# Sheet1.net
KiCad netlist of a schematic drawn in Altium Designer
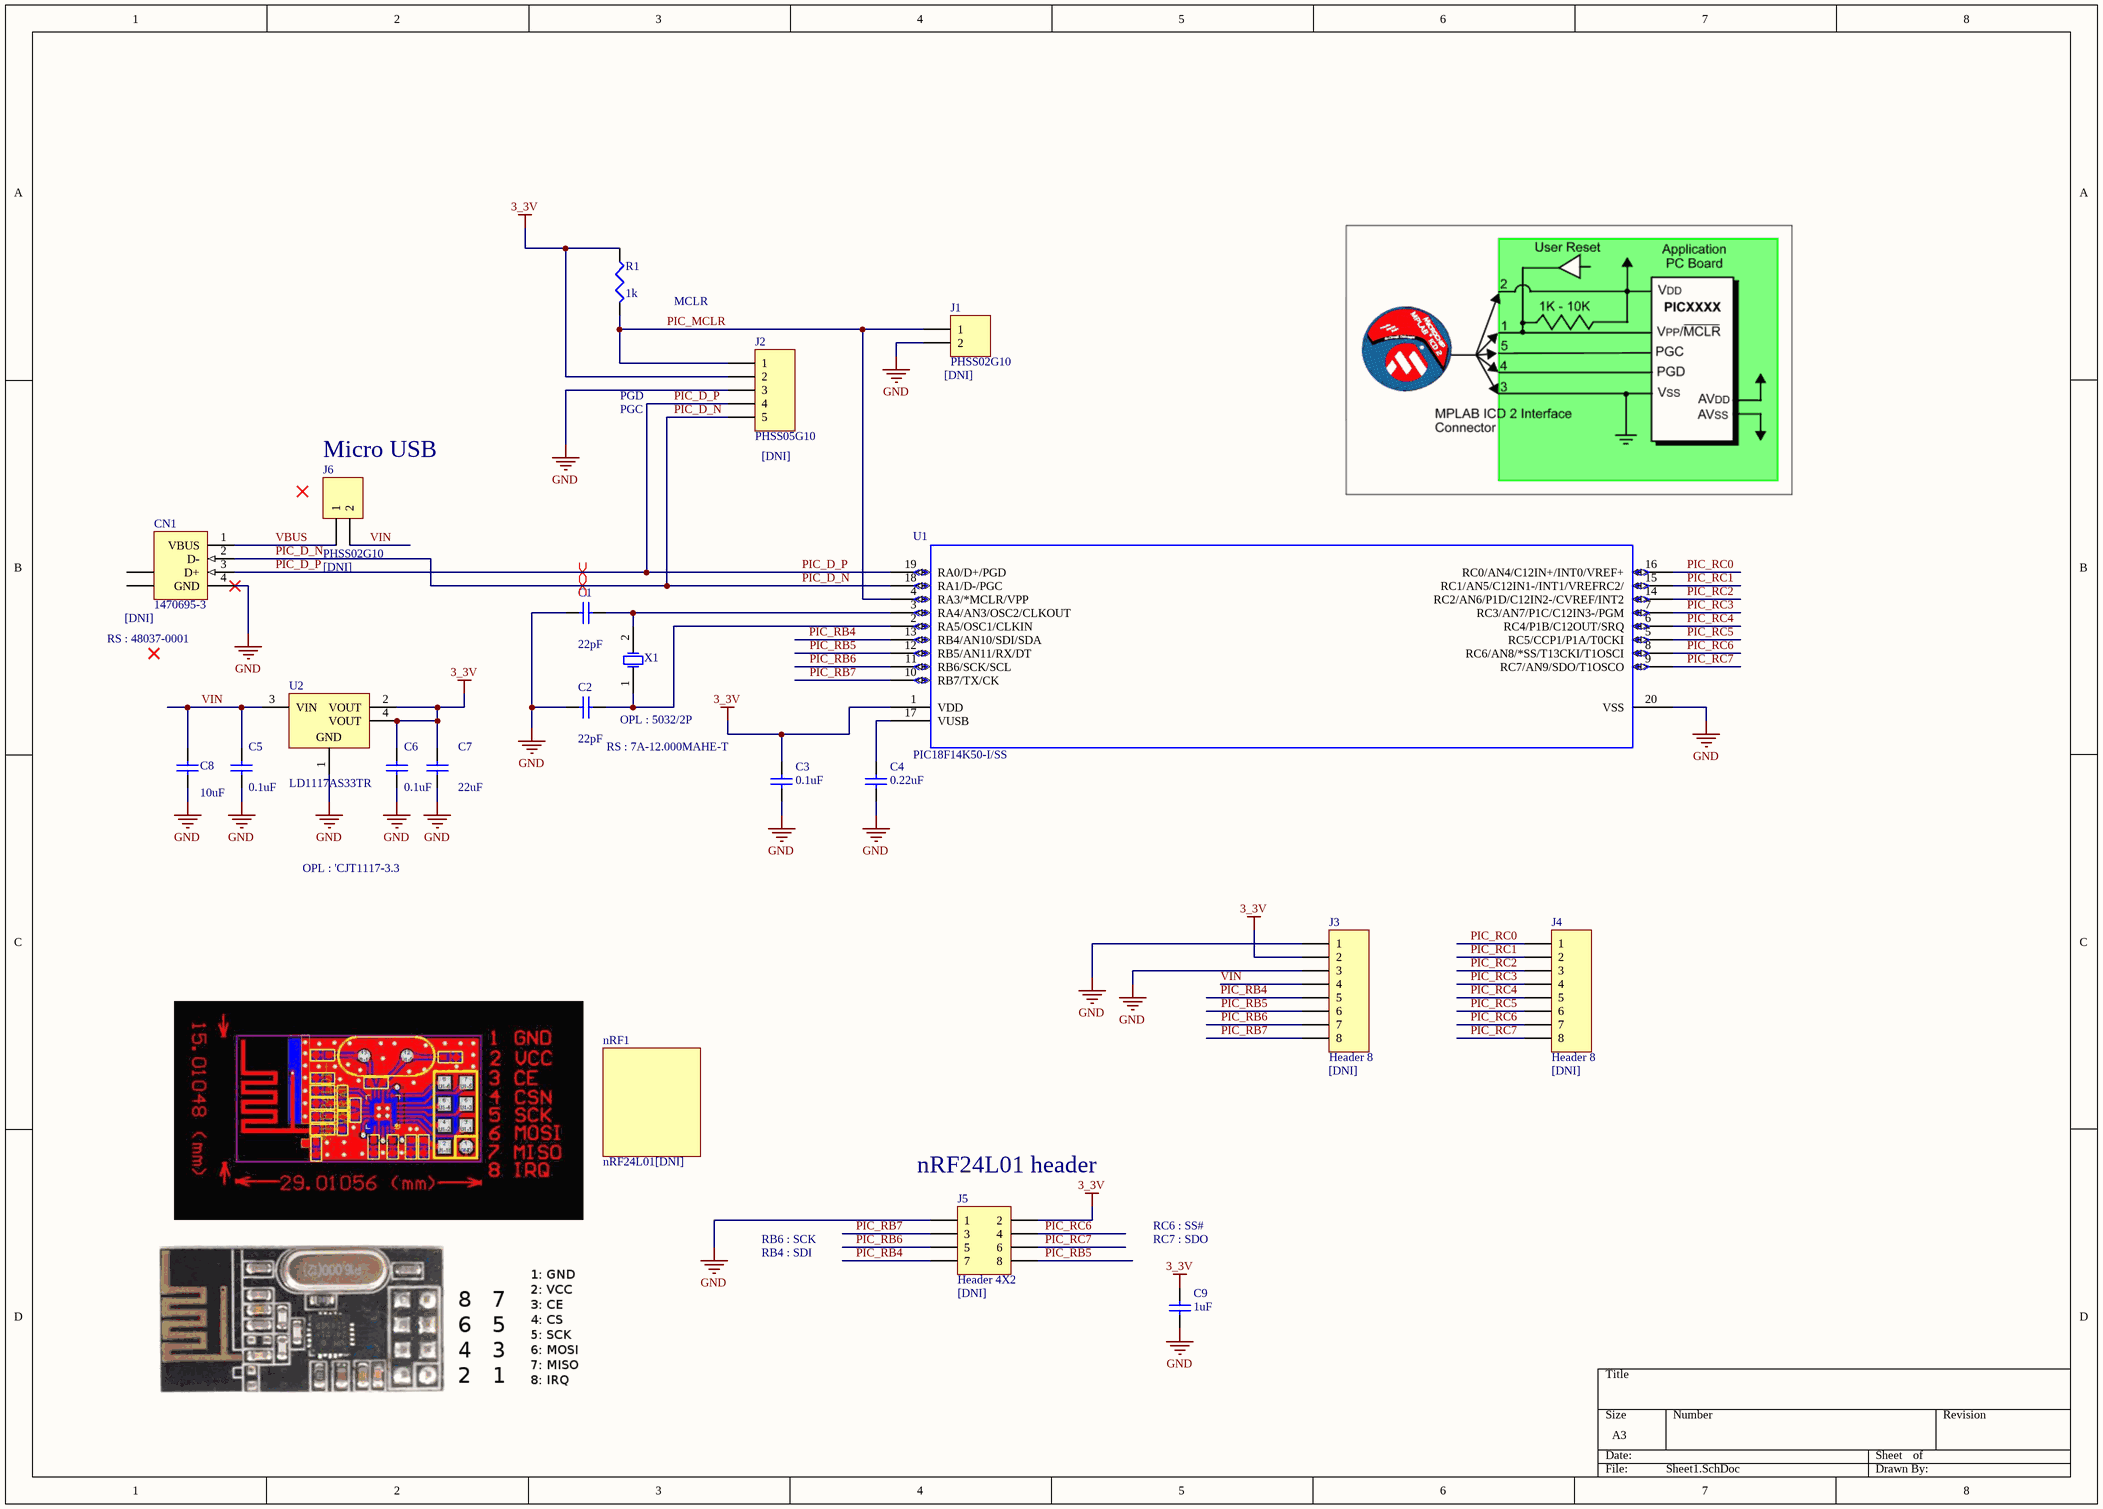
[diagram p0: Sheet1.SchDoc]

(export (version "E")
  (design (tool "Eeschema 10.0.6"))
  (components
    (comp (ref "C1")
      (value "22pF")
      (footprint "PcbLib:CHIP1608")
      (description "Capacitor (Semiconductor SIM Model)")
      (fields (field (name "Comment") "CC0603KRX7R9BB223") (field (name "PUBLISHER") "Altium Limited"))
      (libsource (lib "Miscellaneous Devices") (part "Cap Semi"))
    )
    (comp (ref "C2")
      (value "22pF")
      (footprint "PcbLib:CHIP1608")
      (description "Capacitor (Semiconductor SIM Model)")
      (fields (field (name "Comment") "CC0603KRX7R9BB223") (field (name "PUBLISHER") "Altium Limited"))
      (libsource (lib "Miscellaneous Devices") (part "Cap Semi"))
    )
    (comp (ref "C3")
      (value "0.1uF")
      (footprint "PcbLib:CHIP1608")
      (description "Capacitor (Semiconductor SIM Model)")
      (fields (field (name "Comment") "CC0603KRX7R9BB104") (field (name "PUBLISHER") "Altium Limited"))
      (libsource (lib "Miscellaneous Devices") (part "Cap Semi"))
    )
    (comp (ref "C4")
      (value "0.22uF")
      (footprint "PcbLib:CHIP1608")
      (description "Capacitor (Semiconductor SIM Model)")
      (fields (field (name "Comment") "CC0603KRX7R8BB224") (field (name "PUBLISHER") "Altium Limited"))
      (libsource (lib "Miscellaneous Devices") (part "Cap Semi"))
    )
    (comp (ref "C5")
      (value "0.1uF")
      (footprint "PcbLib:CHIP1608")
      (description "Capacitor (Semiconductor SIM Model)")
      (fields (field (name "Comment") "CC0603KRX7R9BB104") (field (name "PUBLISHER") "Altium Limited"))
      (libsource (lib "Miscellaneous Devices") (part "Cap Semi"))
    )
    (comp (ref "C6")
      (value "0.1uF")
      (footprint "PcbLib:CHIP1608")
      (description "Capacitor (Semiconductor SIM Model)")
      (fields (field (name "Comment") "CC0603KRX7R9BB104") (field (name "PUBLISHER") "Altium Limited"))
      (libsource (lib "Miscellaneous Devices") (part "Cap Semi"))
    )
    (comp (ref "C7")
      (value "22uF")
      (footprint "PcbLib:CHIP3216")
      (description "Capacitor (Semiconductor SIM Model)")
      (fields (field (name "Comment") "TAJA226K010RNJ") (field (name "PUBLISHER") "Altium Limited"))
      (libsource (lib "Miscellaneous Devices") (part "Cap Semi"))
    )
    (comp (ref "C8")
      (value "10uF")
      (footprint "PcbLib:CHIP3216")
      (description "Capacitor (Semiconductor SIM Model)")
      (fields (field (name "Comment") "CC1206KKX5R8BB106") (field (name "PUBLISHER") "Altium Limited"))
      (libsource (lib "Miscellaneous Devices") (part "Cap Semi"))
    )
    (comp (ref "C9")
      (value "1uF")
      (footprint "PcbLib:CHIP1608")
      (description "Capacitor (Semiconductor SIM Model)")
      (fields (field (name "Comment") "CC0603KRX7R8BB105") (field (name "PUBLISHER") "Altium Limited"))
      (libsource (lib "Miscellaneous Devices") (part "Cap Semi"))
    )
    (comp (ref "CN1")
      (value "1470695-3")
      (footprint "PcbLib:UP2-AH-1-TH")
      (description "USB 1.1, Right Angle, SMT, A Type, Plug, 4 Position, Black")
      (fields (field (name "ASSEMBLY") "[DNI]") (field (name "PUBLISHER") "Altium Limited"))
      (libsource (lib "AMP Serial Bus USB") (part "1470695-3"))
    )
    (comp (ref "J1")
      (value "PHSS02G10")
      (footprint "PcbLib:HDR1X2")
      (description "Header, 2-Pin")
      (fields (field (name "ASSEMBLY") "[DNI]") (field (name "PUBLISHER") "Altium Limited"))
      (libsource (lib "Miscellaneous Connectors") (part "Header 2"))
    )
    (comp (ref "J2")
      (value "PHSS05G10")
      (footprint "PcbLib:HDR1X5")
      (description "Header, 5-Pin")
      (fields (field (name "ASSEMBLY") "[DNI]") (field (name "PUBLISHER") "Altium Limited"))
      (libsource (lib "Miscellaneous Connectors") (part "Header 5"))
    )
    (comp (ref "J3")
      (value "Header 8")
      (footprint "PcbLib:HDR1X8")
      (description "Header, 8-Pin")
      (fields (field (name "ASSEMBLY") "[DNI]") (field (name "PUBLISHER") "Altium Limited"))
      (libsource (lib "Miscellaneous Connectors") (part "Header 8"))
    )
    (comp (ref "J4")
      (value "Header 8")
      (footprint "PcbLib:HDR1X8")
      (description "Header, 8-Pin")
      (fields (field (name "ASSEMBLY") "[DNI]") (field (name "PUBLISHER") "Altium Limited"))
      (libsource (lib "Miscellaneous Connectors") (part "Header 8"))
    )
    (comp (ref "J5")
      (value "Header 4X2")
      (footprint "PcbLib:HDR2X4")
      (description "Header, 4-Pin, Dual row")
      (fields (field (name "ASSEMBLY") "[DNI]") (field (name "PUBLISHER") "Altium Limited"))
      (libsource (lib "Miscellaneous Connectors") (part "Header 4X2"))
    )
    (comp (ref "J6")
      (value "PHSS02G10")
      (footprint "PcbLib:HDR1X2")
      (description "Header, 2-Pin")
      (fields (field (name "ASSEMBLY") "[DNI]") (field (name "PUBLISHER") "Altium Limited"))
      (libsource (lib "") (part "Header 2_1"))
    )
    (comp (ref "nRF1")
      (value "nRF24L01[DNI]")
      (footprint "nRF24L01")
      (libsource (lib "Schlib") (part "nRF24L01"))
    )
    (comp (ref "R1")
      (value "1k")
      (footprint "PcbLib:CHIP1608")
      (description "Resistor")
      (fields (field (name "Comment") "RC0603JR-071KL") (field (name "PUBLISHER") "Altium Limited"))
      (libsource (lib "Miscellaneous Devices") (part "Res3"))
    )
    (comp (ref "U1")
      (value "PIC18F14K50-I/SS")
      (footprint "PcbLib:PIC18F14K50-SS")
      (description "MICROCHIPS")
      (libsource (lib "Schlib1") (part "PIC18F14K50"))
    )
    (comp (ref "U2")
      (value "LD1117AS33TR")
      (footprint "SOT-223_N")
      (description "1A, Low Drop Positive Voltage Regulator, 3.3V, 4-Pin SOT-223, Tape and Reel")
      (libsource (lib "STMicroelectronics Power Management Linear Regulator") (part "LD1117AS33TR"))
    )
    (comp (ref "X1")
      (value "445C33C12M00000")
      (footprint "445C33C12M00000")
      (description "MEC")
      (libsource (lib "Schlib1") (part "ABLS-25.000MHZ-B2F-T"))
    )
  )
  (nets
    (net (code "1") (name "/PIC_D_N") (class "Default")
      (node (ref "CN1") (pin "2") (pinfunction "D-_2") (pintype "input"))
      (node (ref "J2") (pin "5") (pinfunction "5_5") (pintype "passive"))
      (node (ref "U1") (pin "18") (pinfunction "RA1/D-/PGC_18") (pintype "bidirectional"))
    )
    (net (code "2") (name "/PIC_D_P") (class "Default")
      (node (ref "CN1") (pin "3") (pinfunction "D+_3") (pintype "input"))
      (node (ref "J2") (pin "4") (pinfunction "4_4") (pintype "passive"))
      (node (ref "U1") (pin "19") (pinfunction "RA0/D+/PGD_19") (pintype "bidirectional"))
    )
    (net (code "3") (name "/PIC_MCLR") (class "Default")
      (node (ref "J1") (pin "1") (pinfunction "1_1") (pintype "passive"))
      (node (ref "J2") (pin "1") (pinfunction "1_1") (pintype "passive"))
      (node (ref "R1") (pin "2") (pinfunction "2_2") (pintype "passive"))
      (node (ref "U1") (pin "4") (pinfunction "RA3/*MCLR/VPP_4") (pintype "bidirectional"))
    )
    (net (code "4") (name "/PIC_RB4") (class "Default")
      (node (ref "J3") (pin "5") (pinfunction "5_5") (pintype "passive"))
      (node (ref "J5") (pin "7") (pinfunction "7_7") (pintype "passive"))
      (node (ref "U1") (pin "13") (pinfunction "RB4/AN10/SDI/SDA_13") (pintype "bidirectional"))
    )
    (net (code "5") (name "/PIC_RB5") (class "Default")
      (node (ref "J3") (pin "6") (pinfunction "6_6") (pintype "passive"))
      (node (ref "J5") (pin "8") (pinfunction "8_8") (pintype "passive"))
      (node (ref "U1") (pin "12") (pinfunction "RB5/AN11/RX/DT_12") (pintype "bidirectional"))
    )
    (net (code "6") (name "/PIC_RB6") (class "Default")
      (node (ref "J3") (pin "7") (pinfunction "7_7") (pintype "passive"))
      (node (ref "J5") (pin "5") (pinfunction "5_5") (pintype "passive"))
      (node (ref "U1") (pin "11") (pinfunction "RB6/SCK/SCL_11") (pintype "bidirectional"))
    )
    (net (code "7") (name "/PIC_RB7") (class "Default")
      (node (ref "J3") (pin "8") (pinfunction "8_8") (pintype "passive"))
      (node (ref "J5") (pin "3") (pinfunction "3_3") (pintype "passive"))
      (node (ref "U1") (pin "10") (pinfunction "RB7/TX/CK_10") (pintype "bidirectional"))
    )
    (net (code "8") (name "/PIC_RC0") (class "Default")
      (node (ref "J4") (pin "1") (pinfunction "1_1") (pintype "passive"))
      (node (ref "U1") (pin "16") (pinfunction "RC0/AN4/C12IN+/INT0/VREF+_16") (pintype "bidirectional"))
    )
    (net (code "9") (name "/PIC_RC1") (class "Default")
      (node (ref "J4") (pin "2") (pinfunction "2_2") (pintype "passive"))
      (node (ref "U1") (pin "15") (pinfunction "RC1/AN5/C12IN1-/INT1/VREFRC2/_15") (pintype "bidirectional"))
    )
    (net (code "10") (name "/PIC_RC2") (class "Default")
      (node (ref "J4") (pin "3") (pinfunction "3_3") (pintype "passive"))
      (node (ref "U1") (pin "14") (pinfunction "RC2/AN6/P1D/C12IN2-/CVREF/INT2_14") (pintype "bidirectional"))
    )
    (net (code "11") (name "/PIC_RC3") (class "Default")
      (node (ref "J4") (pin "4") (pinfunction "4_4") (pintype "passive"))
      (node (ref "U1") (pin "7") (pinfunction "RC3/AN7/P1C/C12IN3-/PGM_7") (pintype "bidirectional"))
    )
    (net (code "12") (name "/PIC_RC4") (class "Default")
      (node (ref "J4") (pin "5") (pinfunction "5_5") (pintype "passive"))
      (node (ref "U1") (pin "6") (pinfunction "RC4/P1B/C12OUT/SRQ_6") (pintype "bidirectional"))
    )
    (net (code "13") (name "/PIC_RC5") (class "Default")
      (node (ref "J4") (pin "6") (pinfunction "6_6") (pintype "passive"))
      (node (ref "U1") (pin "5") (pinfunction "RC5/CCP1/P1A/T0CKI_5") (pintype "bidirectional"))
    )
    (net (code "14") (name "/PIC_RC6") (class "Default")
      (node (ref "J4") (pin "7") (pinfunction "7_7") (pintype "passive"))
      (node (ref "J5") (pin "4") (pinfunction "4_4") (pintype "passive"))
      (node (ref "U1") (pin "8") (pinfunction "RC6/AN8/*SS/T13CKI/T1OSCI_8") (pintype "bidirectional"))
    )
    (net (code "15") (name "/PIC_RC7") (class "Default")
      (node (ref "J4") (pin "8") (pinfunction "8_8") (pintype "passive"))
      (node (ref "J5") (pin "6") (pinfunction "6_6") (pintype "passive"))
      (node (ref "U1") (pin "9") (pinfunction "RC7/AN9/SDO/T1OSCO_9") (pintype "bidirectional"))
    )
    (net (code "16") (name "/VBUS") (class "Default")
      (node (ref "CN1") (pin "1") (pinfunction "VBUS_1") (pintype "power_in"))
      (node (ref "J6") (pin "1") (pinfunction "1_1") (pintype "passive"))
    )
    (net (code "17") (name "/VIN") (class "Default")
      (node (ref "C5") (pin "2") (pinfunction "2_2") (pintype "passive"))
      (node (ref "C8") (pin "2") (pinfunction "2_2") (pintype "passive"))
      (node (ref "J3") (pin "4") (pinfunction "4_4") (pintype "passive"))
      (node (ref "J6") (pin "2") (pinfunction "2_2") (pintype "passive"))
      (node (ref "U2") (pin "3") (pinfunction "VIN_3") (pintype "power_in"))
    )
    (net (code "18") (name "3_3V") (class "Default")
      (node (ref "C3") (pin "2") (pinfunction "2_2") (pintype "passive"))
      (node (ref "C6") (pin "2") (pinfunction "2_2") (pintype "passive"))
      (node (ref "C7") (pin "2") (pinfunction "2_2") (pintype "passive"))
      (node (ref "C9") (pin "2") (pinfunction "2_2") (pintype "passive"))
      (node (ref "J2") (pin "2") (pinfunction "2_2") (pintype "passive"))
      (node (ref "J3") (pin "2") (pinfunction "2_2") (pintype "passive"))
      (node (ref "J5") (pin "2") (pinfunction "2_2") (pintype "passive"))
      (node (ref "R1") (pin "1") (pinfunction "1_1") (pintype "passive"))
      (node (ref "U1") (pin "1") (pinfunction "VDD_1") (pintype "power_in"))
      (node (ref "U2") (pin "2") (pinfunction "VOUT_2") (pintype "power_in"))
      (node (ref "U2") (pin "4") (pinfunction "VOUT_4") (pintype "power_in"))
    )
    (net (code "19") (name "GND") (class "Default")
      (node (ref "C1") (pin "1") (pinfunction "1_1") (pintype "passive"))
      (node (ref "C2") (pin "1") (pinfunction "1_1") (pintype "passive"))
      (node (ref "C3") (pin "1") (pinfunction "1_1") (pintype "passive"))
      (node (ref "C4") (pin "1") (pinfunction "1_1") (pintype "passive"))
      (node (ref "C5") (pin "1") (pinfunction "1_1") (pintype "passive"))
      (node (ref "C6") (pin "1") (pinfunction "1_1") (pintype "passive"))
      (node (ref "C7") (pin "1") (pinfunction "1_1") (pintype "passive"))
      (node (ref "C8") (pin "1") (pinfunction "1_1") (pintype "passive"))
      (node (ref "C9") (pin "1") (pinfunction "1_1") (pintype "passive"))
      (node (ref "CN1") (pin "4") (pinfunction "GND_4") (pintype "power_in"))
      (node (ref "J1") (pin "2") (pinfunction "2_2") (pintype "passive"))
      (node (ref "J2") (pin "3") (pinfunction "3_3") (pintype "passive"))
      (node (ref "J3") (pin "1") (pinfunction "1_1") (pintype "passive"))
      (node (ref "J3") (pin "3") (pinfunction "3_3") (pintype "passive"))
      (node (ref "J5") (pin "1") (pinfunction "1_1") (pintype "passive"))
      (node (ref "U1") (pin "20") (pinfunction "VSS_20") (pintype "power_in"))
      (node (ref "U2") (pin "1") (pinfunction "GND_1") (pintype "power_in"))
    )
    (net (code "20") (name "Net-(U1-RA4{slash}AN3{slash}OSC2{slash}CLKOUT)") (class "Default")
      (node (ref "C1") (pin "2") (pinfunction "2_2") (pintype "passive"))
      (node (ref "U1") (pin "3") (pinfunction "RA4/AN3/OSC2/CLKOUT_3") (pintype "bidirectional"))
      (node (ref "X1") (pin "2") (pinfunction "OSC2_2") (pintype "passive"))
    )
    (net (code "21") (name "Net-(U1-RA5{slash}OSC1{slash}CLKIN)") (class "Default")
      (node (ref "C2") (pin "2") (pinfunction "2_2") (pintype "passive"))
      (node (ref "U1") (pin "2") (pinfunction "RA5/OSC1/CLKIN_2") (pintype "bidirectional"))
      (node (ref "X1") (pin "1") (pinfunction "OSC1_1") (pintype "passive"))
    )
    (net (code "22") (name "Net-(U1-VUSB)") (class "Default")
      (node (ref "C4") (pin "2") (pinfunction "2_2") (pintype "passive"))
      (node (ref "U1") (pin "17") (pinfunction "VUSB_17") (pintype "power_in"))
    )
    (net (code "23") (name "unconnected-(CN1-SHLD-Pad5)") (class "Default")
      (node (ref "CN1") (pin "5") (pinfunction "SHLD_5") (pintype "passive"))
    )
    (net (code "24") (name "unconnected-(CN1-SHLD-Pad6)") (class "Default")
      (node (ref "CN1") (pin "6") (pinfunction "SHLD_6") (pintype "passive"))
    )
  )
)
